# KMO_IO_MV2_1.net
KiCad netlist of a schematic drawn in EAGLE
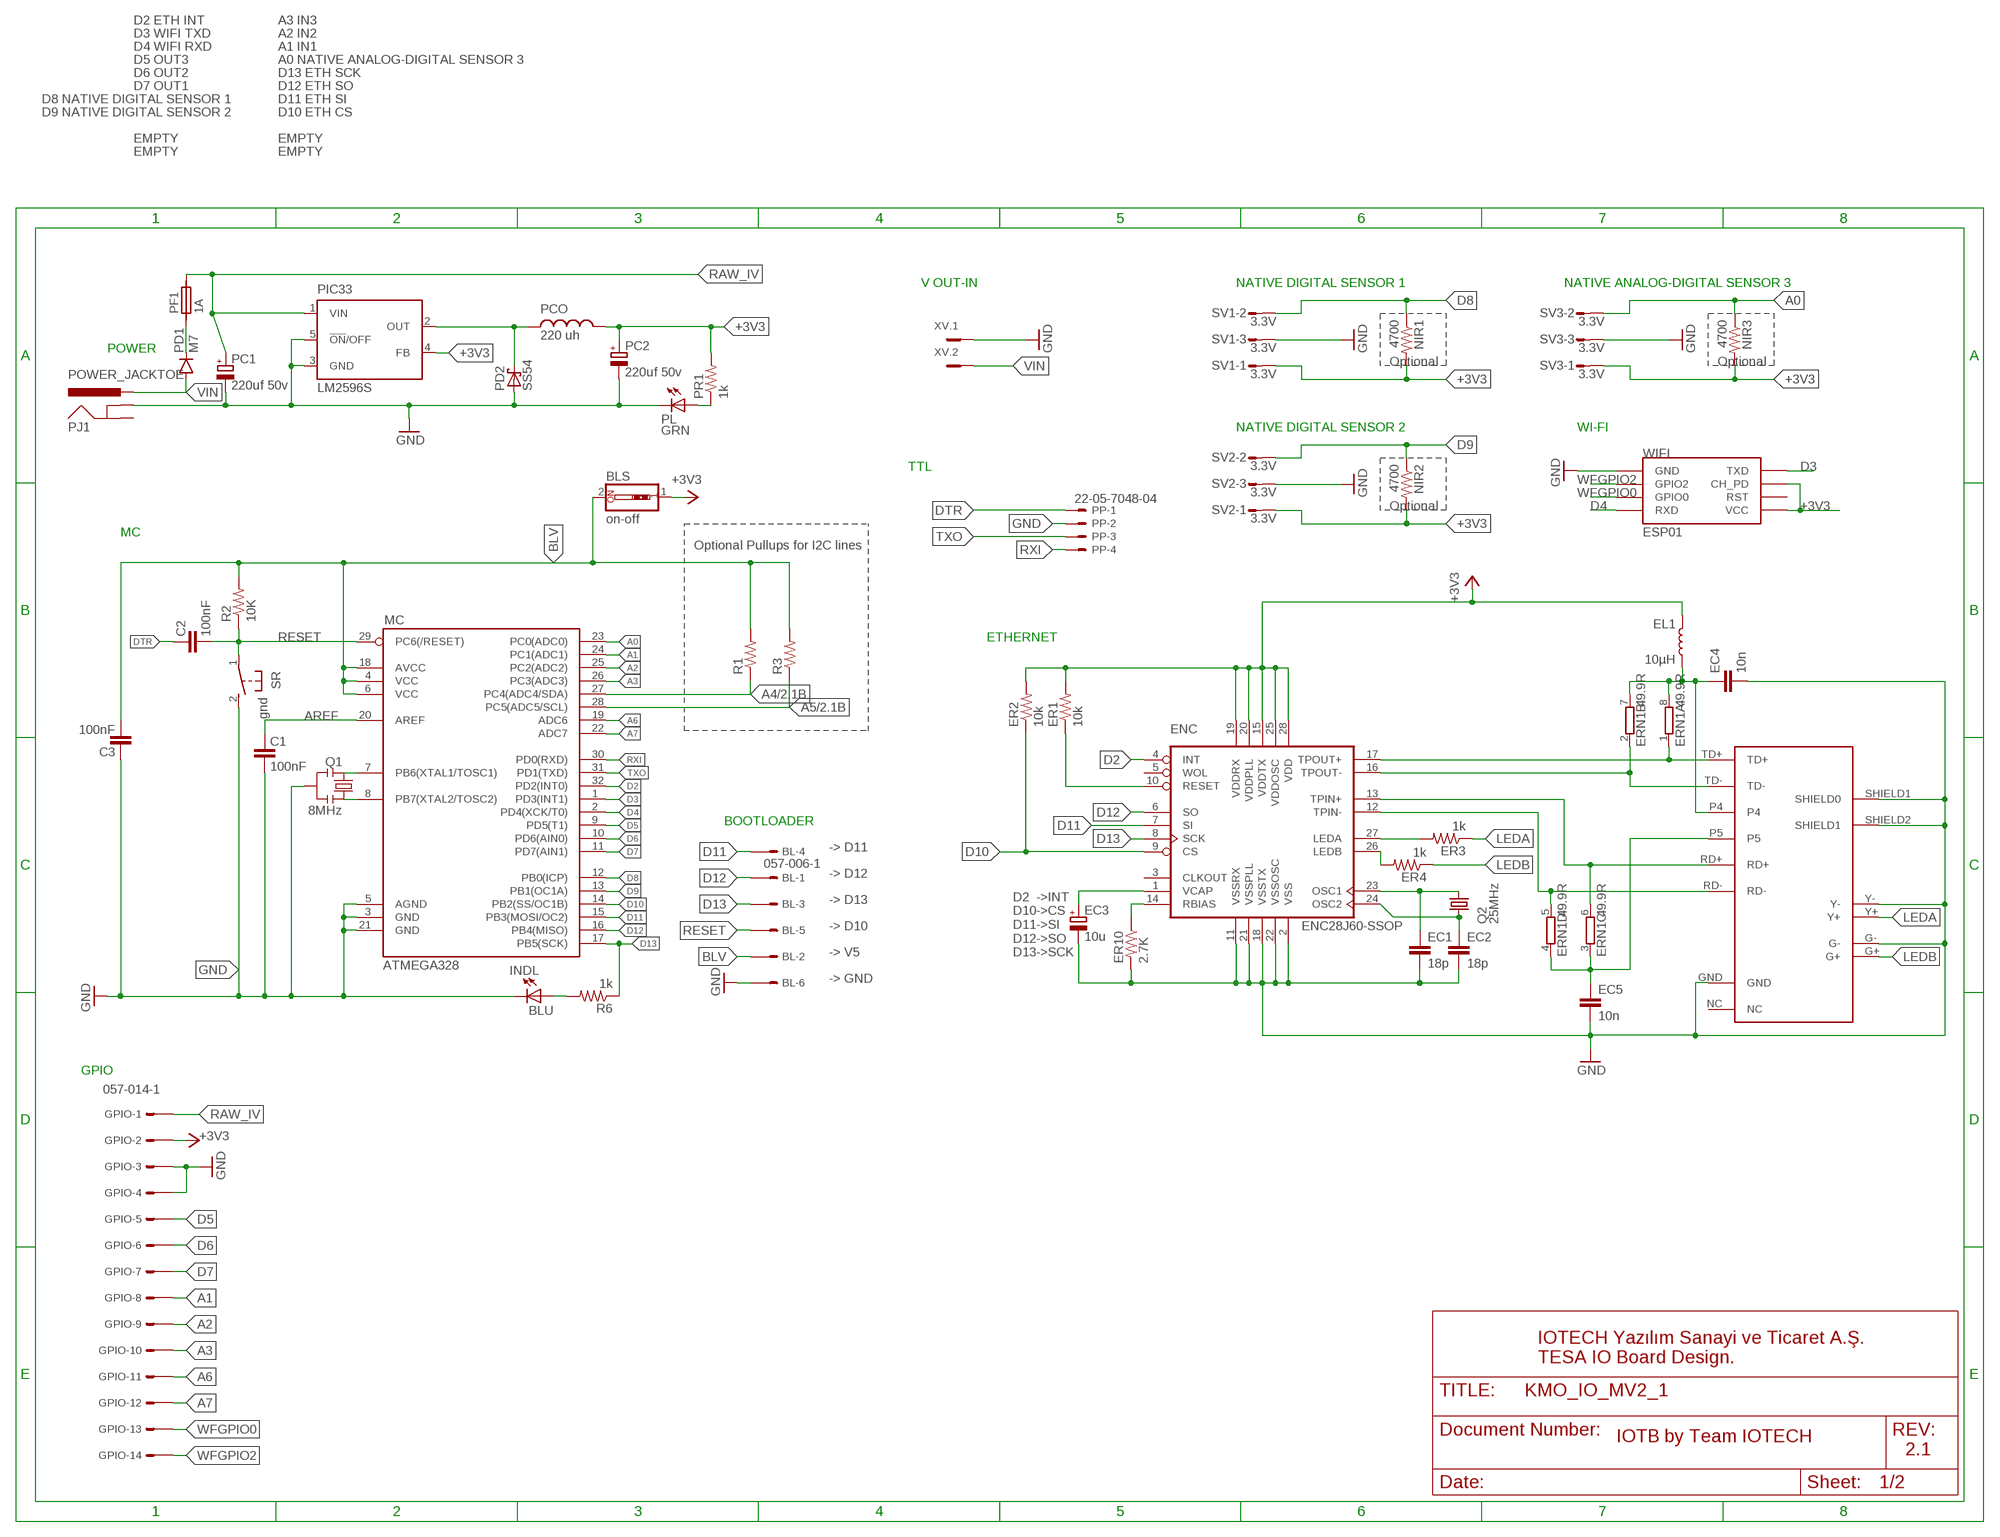
[diagram p0: schematic, sheet 1]
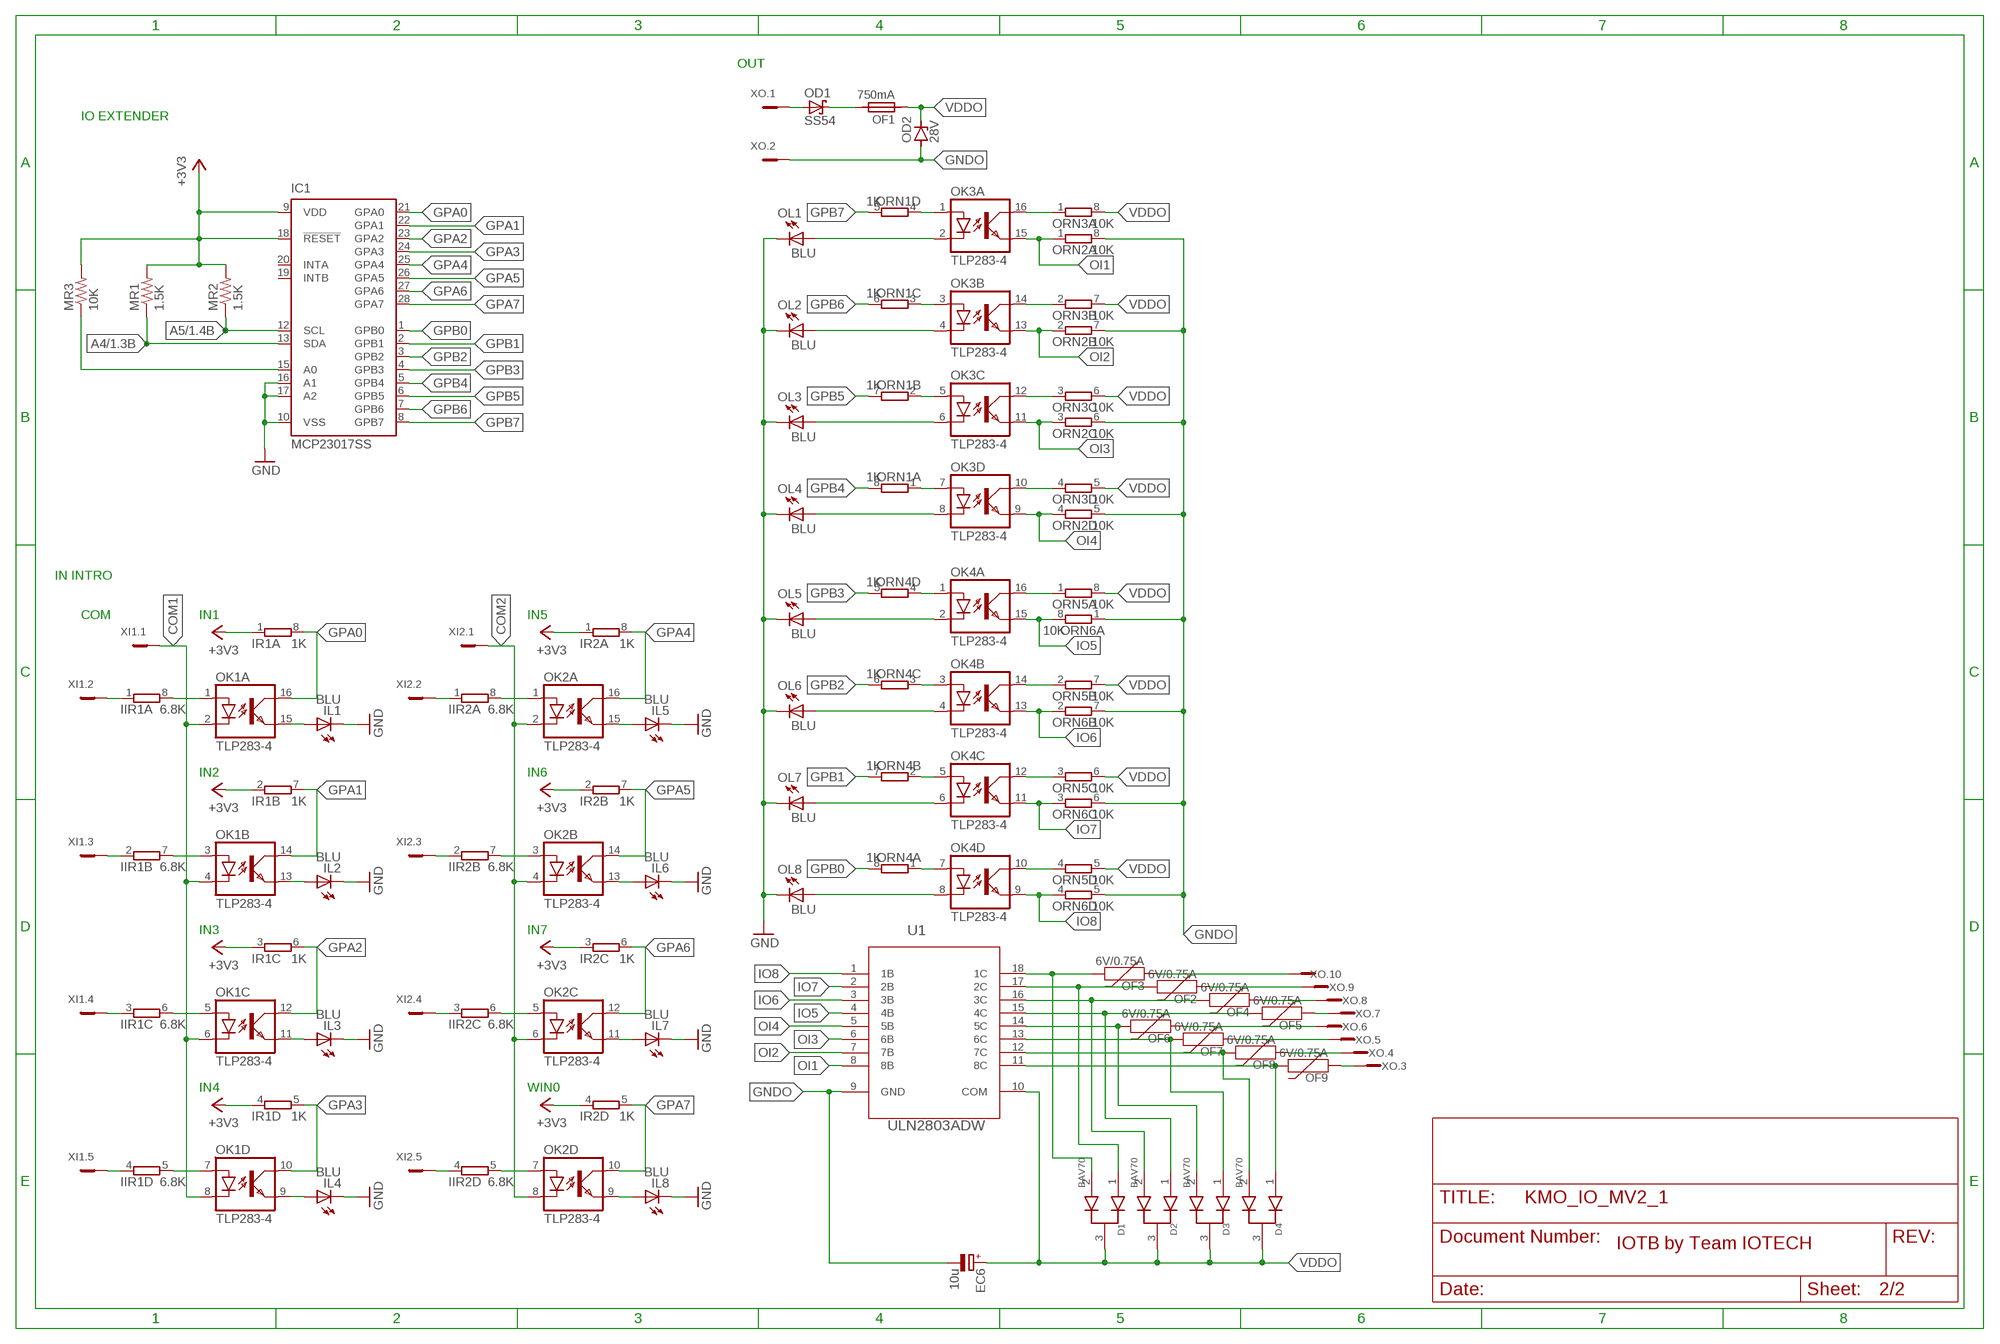
[diagram p1: schematic, sheet 2]

(export (version "E")
  (design (tool "Eeschema 10.0.6"))
  (components
    (comp (ref "BL")
      (value "057-006-1")
      (footprint "eagle-import:057-006-1")
      (libsource (lib "eagle-import") (part "057-006-1"))
    )
    (comp (ref "BLS")
      (value "on-off")
      (footprint "eagle-import:EDG-01")
      (libsource (lib "eagle-import") (part "SW_DIP-1"))
    )
    (comp (ref "C1")
      (value "100nF")
      (footprint "eagle-import:0805")
      (libsource (lib "eagle-import") (part "CAP0805"))
    )
    (comp (ref "C2")
      (value "100nF")
      (footprint "eagle-import:0805")
      (libsource (lib "eagle-import") (part "CAP0805"))
    )
    (comp (ref "C3")
      (value "100nF")
      (footprint "eagle-import:0805")
      (libsource (lib "eagle-import") (part "CAP0805"))
    )
    (comp (ref "EC1")
      (value "18p")
      (footprint "eagle-import:0805")
      (libsource (lib "eagle-import") (part "CAP0805"))
    )
    (comp (ref "EC2")
      (value "18p")
      (footprint "eagle-import:0805")
      (libsource (lib "eagle-import") (part "CAP0805"))
    )
    (comp (ref "EC3")
      (value "10u")
      (footprint "eagle-import:CT3216")
      (libsource (lib "eagle-import") (part "CPOL-EUCT3216"))
    )
    (comp (ref "EC4")
      (value "10n")
      (footprint "eagle-import:0805")
      (libsource (lib "eagle-import") (part "CAP0805"))
    )
    (comp (ref "EC5")
      (value "10n")
      (footprint "eagle-import:0805")
      (libsource (lib "eagle-import") (part "CAP0805"))
    )
    (comp (ref "EL1")
      (value "10µH")
      (footprint "eagle-import:0805")
      (libsource (lib "eagle-import") (part "INDUCTOR-0805-3.3UH"))
    )
    (comp (ref "ENC")
      (value "ENC28J60-SSOP")
      (footprint "eagle-import:SSOP28")
      (libsource (lib "eagle-import") (part "ENC28J60-SSOP"))
    )
    (comp (ref "ER1")
      (value "10k")
      (footprint "eagle-import:0805")
      (libsource (lib "eagle-import") (part "RESISTOR0805-RES"))
    )
    (comp (ref "ER2")
      (value "10k")
      (footprint "eagle-import:0805")
      (libsource (lib "eagle-import") (part "RESISTOR0805-RES"))
    )
    (comp (ref "ER3")
      (value "1k")
      (footprint "eagle-import:0805")
      (libsource (lib "eagle-import") (part "RESISTOR0805-RES"))
    )
    (comp (ref "ER4")
      (value "1k")
      (footprint "eagle-import:0805")
      (libsource (lib "eagle-import") (part "RESISTOR0805-RES"))
    )
    (comp (ref "ER10")
      (value "2.7K")
      (footprint "eagle-import:0805")
      (libsource (lib "eagle-import") (part "RESISTOR0805-RES"))
    )
    (comp (ref "ERN1")
      (value "49.9R")
      (footprint "eagle-import:0603-ARV")
      (libsource (lib "eagle-import") (part "4R-N0603-ARV"))
    )
    (comp (ref "GPIO")
      (value "057-014-1")
      (footprint "eagle-import:057-014-1")
      (libsource (lib "eagle-import") (part "057-014-1"))
    )
    (comp (ref "INDL")
      (value "BLU")
      (footprint "eagle-import:CHIP-LED0805")
      (libsource (lib "eagle-import") (part "LEDCHIP-LED0805"))
    )
    (comp (ref "MC")
      (value "ATMEGA328")
      (footprint "eagle-import:TQFP32-08")
      (libsource (lib "eagle-import") (part "ATMEGA168"))
    )
    (comp (ref "NIR1")
      (value "4700")
      (footprint "eagle-import:0805")
      (libsource (lib "eagle-import") (part "RESISTOR0805-RES"))
    )
    (comp (ref "NIR2")
      (value "4700")
      (footprint "eagle-import:0805")
      (libsource (lib "eagle-import") (part "RESISTOR0805-RES"))
    )
    (comp (ref "NIR3")
      (value "4700")
      (footprint "eagle-import:0805")
      (libsource (lib "eagle-import") (part "RESISTOR0805-RES"))
    )
    (comp (ref "PC1")
      (value "220uf 50v")
      (footprint "eagle-import:140CLH-1010")
      (libsource (lib "eagle-import") (part "CPOL-EU140CLH-1010"))
    )
    (comp (ref "PC2")
      (value "220uf 50v")
      (footprint "eagle-import:140CLH-1010")
      (libsource (lib "eagle-import") (part "CPOL-EU140CLH-1010"))
    )
    (comp (ref "PCO")
      (value "220 uh")
      (footprint "eagle-import:MSS1260")
      (libsource (lib "eagle-import") (part "MSS1260"))
    )
    (comp (ref "PD1")
      (value "M7")
      (footprint "eagle-import:SMA-DIODE")
      (libsource (lib "eagle-import") (part "DIODESMA"))
    )
    (comp (ref "PD2")
      (value "SS54")
      (footprint "eagle-import:SMB")
      (libsource (lib "eagle-import") (part "SCHOTTKY-DIODESMD"))
    )
    (comp (ref "PF1")
      (value "1A")
      (footprint "eagle-import:1820")
      (libsource (lib "eagle-import") (part "SIBA194600"))
    )
    (comp (ref "PIC33")
      (value "LM2596S")
      (footprint "eagle-import:TO263-5")
      (fields (field (name "MF") "NATIONAL SEMICONDUCTOR") (field (name "MPN") "LM2596S-ADJ/NOPB"))
      (libsource (lib "eagle-import") (part "LM2596S"))
    )
    (comp (ref "PJ1")
      (value "POWER_JACKTOE")
      (footprint "eagle-import:POWER_JACK_SMD_OVERPASTE_TOE")
      (libsource (lib "eagle-import") (part "POWER_JACKTOE"))
    )
    (comp (ref "PL")
      (value "GRN")
      (footprint "eagle-import:CHIP-LED0805")
      (libsource (lib "eagle-import") (part "LEDCHIP-LED0805"))
    )
    (comp (ref "PP")
      (value "22-05-7048-04")
      (footprint "eagle-import:7395-04")
      (fields (field (name "MF") "MOLEX"))
      (libsource (lib "eagle-import") (part "22-?-0405-7048"))
    )
    (comp (ref "PR1")
      (value "1k")
      (footprint "eagle-import:0805")
      (libsource (lib "eagle-import") (part "RESISTOR0805-RES"))
    )
    (comp (ref "Q1")
      (value "8MHz")
      (footprint "eagle-import:RESONATOR-SMD-1_1")
      (libsource (lib "eagle-import") (part "RESONATOR1{colon}1"))
    )
    (comp (ref "Q2")
      (value "25MHz")
      (footprint "eagle-import:5.0X3.2_2")
      (libsource (lib "eagle-import") (part "KX-9B"))
    )
    (comp (ref "R1")
      (value "RESISTOR0805-RES")
      (footprint "eagle-import:0805")
      (libsource (lib "eagle-import") (part "RESISTOR0805-RES"))
    )
    (comp (ref "R2")
      (value "10K")
      (footprint "eagle-import:0805")
      (libsource (lib "eagle-import") (part "RESISTOR0805-RES"))
    )
    (comp (ref "R3")
      (value "RESISTOR0805-RES")
      (footprint "eagle-import:0805")
      (libsource (lib "eagle-import") (part "RESISTOR0805-RES"))
    )
    (comp (ref "R6")
      (value "1k")
      (footprint "eagle-import:0805")
      (libsource (lib "eagle-import") (part "RESISTOR0805-RES"))
    )
    (comp (ref "SR")
      (value "gnd")
      (footprint "eagle-import:B3F-31XX")
      (fields (field (name "MPN") "B3F-3100"))
      (libsource (lib "eagle-import") (part "31-XX"))
    )
    (comp (ref "SV1")
      (value "3.3V")
      (footprint "eagle-import:S03P")
      (libsource (lib "eagle-import") (part "S03P"))
    )
    (comp (ref "SV2")
      (value "3.3V")
      (footprint "eagle-import:S03P")
      (libsource (lib "eagle-import") (part "S03P"))
    )
    (comp (ref "SV3")
      (value "3.3V")
      (footprint "eagle-import:S03P")
      (libsource (lib "eagle-import") (part "S03P"))
    )
    (comp (ref "U$2")
      (value "HR911105A")
      (footprint "eagle-import:RJ45")
      (libsource (lib "eagle-import") (part "HR911105A"))
    )
    (comp (ref "WIFI")
      (value "ESP01")
      (footprint "eagle-import:ESP01")
      (libsource (lib "eagle-import") (part "ESP01"))
    )
    (comp (ref "XV")
      (value "MC2")
      (footprint "eagle-import:MC2")
      (libsource (lib "eagle-import") (part "MC2"))
    )
    (comp (ref "D1")
      (value "BAV70")
      (footprint "eagle-import:SOT-23-3")
      (fields (field (name "MF") "Multicomp") (field (name "MP") "BAV70+"))
      (libsource (lib "eagle-import") (part "BAV70"))
    )
    (comp (ref "D2")
      (value "BAV70")
      (footprint "eagle-import:SOT-23-3")
      (fields (field (name "MF") "Multicomp") (field (name "MP") "BAV70+"))
      (libsource (lib "eagle-import") (part "BAV70"))
    )
    (comp (ref "D3")
      (value "BAV70")
      (footprint "eagle-import:SOT-23-3")
      (fields (field (name "MF") "Multicomp") (field (name "MP") "BAV70+"))
      (libsource (lib "eagle-import") (part "BAV70"))
    )
    (comp (ref "D4")
      (value "BAV70")
      (footprint "eagle-import:SOT-23-3")
      (fields (field (name "MF") "Multicomp") (field (name "MP") "BAV70+"))
      (libsource (lib "eagle-import") (part "BAV70"))
    )
    (comp (ref "EC6")
      (value "10u")
      (footprint "eagle-import:CT3216")
      (libsource (lib "eagle-import") (part "CPOL-EUCT3216"))
    )
    (comp (ref "IC1")
      (value "MCP23017SS")
      (footprint "eagle-import:SSOP28")
      (fields (field (name "MF") "MICROCHIP") (field (name "MPN") "MCP23017-E/SS"))
      (libsource (lib "eagle-import") (part "MCP23017SS"))
    )
    (comp (ref "IIR1")
      (value "6.8K")
      (footprint "eagle-import:0603-ARV")
      (libsource (lib "eagle-import") (part "4R-N0603-ARV"))
    )
    (comp (ref "IIR2")
      (value "6.8K")
      (footprint "eagle-import:0603-ARV")
      (libsource (lib "eagle-import") (part "4R-N0603-ARV"))
    )
    (comp (ref "IL1")
      (value "BLU")
      (footprint "eagle-import:CHIP-LED0805")
      (libsource (lib "eagle-import") (part "LEDCHIP-LED0805"))
    )
    (comp (ref "IL2")
      (value "BLU")
      (footprint "eagle-import:CHIP-LED0805")
      (libsource (lib "eagle-import") (part "LEDCHIP-LED0805"))
    )
    (comp (ref "IL3")
      (value "BLU")
      (footprint "eagle-import:CHIP-LED0805")
      (libsource (lib "eagle-import") (part "LEDCHIP-LED0805"))
    )
    (comp (ref "IL4")
      (value "BLU")
      (footprint "eagle-import:CHIP-LED0805")
      (libsource (lib "eagle-import") (part "LEDCHIP-LED0805"))
    )
    (comp (ref "IL5")
      (value "BLU")
      (footprint "eagle-import:CHIP-LED0805")
      (libsource (lib "eagle-import") (part "LEDCHIP-LED0805"))
    )
    (comp (ref "IL6")
      (value "BLU")
      (footprint "eagle-import:CHIP-LED0805")
      (libsource (lib "eagle-import") (part "LEDCHIP-LED0805"))
    )
    (comp (ref "IL7")
      (value "BLU")
      (footprint "eagle-import:CHIP-LED0805")
      (libsource (lib "eagle-import") (part "LEDCHIP-LED0805"))
    )
    (comp (ref "IL8")
      (value "BLU")
      (footprint "eagle-import:CHIP-LED0805")
      (libsource (lib "eagle-import") (part "LEDCHIP-LED0805"))
    )
    (comp (ref "IR1")
      (value "1K")
      (footprint "eagle-import:0603-ARV")
      (libsource (lib "eagle-import") (part "4R-N0603-ARV"))
    )
    (comp (ref "IR2")
      (value "1K")
      (footprint "eagle-import:0603-ARV")
      (libsource (lib "eagle-import") (part "4R-N0603-ARV"))
    )
    (comp (ref "MR1")
      (value "1.5K")
      (footprint "eagle-import:0805")
      (libsource (lib "eagle-import") (part "RESISTOR0805-RES"))
    )
    (comp (ref "MR2")
      (value "1.5K")
      (footprint "eagle-import:0805")
      (libsource (lib "eagle-import") (part "RESISTOR0805-RES"))
    )
    (comp (ref "MR3")
      (value "10K")
      (footprint "eagle-import:0805")
      (libsource (lib "eagle-import") (part "RESISTOR0805-RES"))
    )
    (comp (ref "OD1")
      (value "SS54")
      (footprint "eagle-import:SMB")
      (libsource (lib "eagle-import") (part "SCHOTTKY-DIODESMD"))
    )
    (comp (ref "OD2")
      (value "28V")
      (footprint "eagle-import:SMB")
      (libsource (lib "eagle-import") (part "ZENER-DIODESMB"))
    )
    (comp (ref "OF1")
      (value "750mA")
      (footprint "eagle-import:1820")
      (libsource (lib "eagle-import") (part "SIBA194600"))
    )
    (comp (ref "OF2")
      (value "6V/0.75A")
      (footprint "eagle-import:1206")
      (libsource (lib "eagle-import") (part "PPTC_0.75A"))
    )
    (comp (ref "OF3")
      (value "6V/0.75A")
      (footprint "eagle-import:1206")
      (libsource (lib "eagle-import") (part "PPTC_0.75A"))
    )
    (comp (ref "OF4")
      (value "6V/0.75A")
      (footprint "eagle-import:1206")
      (libsource (lib "eagle-import") (part "PPTC_0.75A"))
    )
    (comp (ref "OF5")
      (value "6V/0.75A")
      (footprint "eagle-import:1206")
      (libsource (lib "eagle-import") (part "PPTC_0.75A"))
    )
    (comp (ref "OF6")
      (value "6V/0.75A")
      (footprint "eagle-import:1206")
      (libsource (lib "eagle-import") (part "PPTC_0.75A"))
    )
    (comp (ref "OF7")
      (value "6V/0.75A")
      (footprint "eagle-import:1206")
      (libsource (lib "eagle-import") (part "PPTC_0.75A"))
    )
    (comp (ref "OF8")
      (value "6V/0.75A")
      (footprint "eagle-import:1206")
      (libsource (lib "eagle-import") (part "PPTC_0.75A"))
    )
    (comp (ref "OF9")
      (value "6V/0.75A")
      (footprint "eagle-import:1206")
      (libsource (lib "eagle-import") (part "PPTC_0.75A"))
    )
    (comp (ref "OK1")
      (value "TLP283-4")
      (footprint "eagle-import:MINI-FLAT-16")
      (fields (field (name "SPICEPREFIX") "O"))
      (libsource (lib "eagle-import") (part "TLP283-4"))
    )
    (comp (ref "OK2")
      (value "TLP283-4")
      (footprint "eagle-import:MINI-FLAT-16")
      (fields (field (name "SPICEPREFIX") "O"))
      (libsource (lib "eagle-import") (part "TLP283-4"))
    )
    (comp (ref "OK3")
      (value "TLP283-4")
      (footprint "eagle-import:MINI-FLAT-16")
      (libsource (lib "eagle-import") (part "TLP283-4"))
    )
    (comp (ref "OK4")
      (value "TLP283-4")
      (footprint "eagle-import:MINI-FLAT-16")
      (libsource (lib "eagle-import") (part "TLP283-4"))
    )
    (comp (ref "OL1")
      (value "BLU")
      (footprint "eagle-import:CHIP-LED0805")
      (libsource (lib "eagle-import") (part "LEDCHIP-LED0805"))
    )
    (comp (ref "OL2")
      (value "BLU")
      (footprint "eagle-import:CHIP-LED0805")
      (libsource (lib "eagle-import") (part "LEDCHIP-LED0805"))
    )
    (comp (ref "OL3")
      (value "BLU")
      (footprint "eagle-import:CHIP-LED0805")
      (libsource (lib "eagle-import") (part "LEDCHIP-LED0805"))
    )
    (comp (ref "OL4")
      (value "BLU")
      (footprint "eagle-import:CHIP-LED0805")
      (libsource (lib "eagle-import") (part "LEDCHIP-LED0805"))
    )
    (comp (ref "OL5")
      (value "BLU")
      (footprint "eagle-import:CHIP-LED0805")
      (libsource (lib "eagle-import") (part "LEDCHIP-LED0805"))
    )
    (comp (ref "OL6")
      (value "BLU")
      (footprint "eagle-import:CHIP-LED0805")
      (libsource (lib "eagle-import") (part "LEDCHIP-LED0805"))
    )
    (comp (ref "OL7")
      (value "BLU")
      (footprint "eagle-import:CHIP-LED0805")
      (libsource (lib "eagle-import") (part "LEDCHIP-LED0805"))
    )
    (comp (ref "OL8")
      (value "BLU")
      (footprint "eagle-import:CHIP-LED0805")
      (libsource (lib "eagle-import") (part "LEDCHIP-LED0805"))
    )
    (comp (ref "ORN1")
      (value "1K")
      (footprint "eagle-import:0603-ARV")
      (libsource (lib "eagle-import") (part "4R-N0603-ARV"))
    )
    (comp (ref "ORN2")
      (value "10K")
      (footprint "eagle-import:0603-ARV")
      (libsource (lib "eagle-import") (part "4R-N0603-ARV"))
    )
    (comp (ref "ORN3")
      (value "10K")
      (footprint "eagle-import:0603-ARV")
      (libsource (lib "eagle-import") (part "4R-N0603-ARV"))
    )
    (comp (ref "ORN4")
      (value "1K")
      (footprint "eagle-import:0603-ARV")
      (libsource (lib "eagle-import") (part "4R-N0603-ARV"))
    )
    (comp (ref "ORN5")
      (value "10K")
      (footprint "eagle-import:0603-ARV")
      (libsource (lib "eagle-import") (part "4R-N0603-ARV"))
    )
    (comp (ref "ORN6")
      (value "10K")
      (footprint "eagle-import:0603-ARV")
      (libsource (lib "eagle-import") (part "4R-N0603-ARV"))
    )
    (comp (ref "U1")
      (value "ULN2803ADW")
      (footprint "eagle-import:SOIC127P1030X265-18N")
      (libsource (lib "eagle-import") (part "ULN2803ADW"))
    )
    (comp (ref "XI1")
      (value "MC5")
      (footprint "eagle-import:MC5")
      (libsource (lib "eagle-import") (part "MC5"))
    )
    (comp (ref "XI2")
      (value "MC5")
      (footprint "eagle-import:MC5")
      (libsource (lib "eagle-import") (part "MC5"))
    )
    (comp (ref "XO")
      (value "MC10")
      (footprint "eagle-import:MC10")
      (libsource (lib "eagle-import") (part "MC10"))
    )
  )
  (nets
    (net (code "1") (name "+3V3") (class "Default")
      (node (ref "BLS") (pin "1") (pinfunction "1_1") (pintype "passive"))
      (node (ref "EL1") (pin "1") (pinfunction "1_1") (pintype "passive"))
      (node (ref "ENC") (pin "15") (pinfunction "VDDTX_15") (pintype "power_in"))
      (node (ref "ENC") (pin "19") (pinfunction "VDDRX_19") (pintype "power_in"))
      (node (ref "ENC") (pin "20") (pinfunction "VDDPLL_20") (pintype "power_in"))
      (node (ref "ENC") (pin "25") (pinfunction "VDDOSC_25") (pintype "power_in"))
      (node (ref "ENC") (pin "28") (pinfunction "VDD_28") (pintype "power_in"))
      (node (ref "ER1") (pin "2") (pinfunction "2_2") (pintype "passive"))
      (node (ref "ER2") (pin "2") (pinfunction "2_2") (pintype "passive"))
      (node (ref "GPIO") (pin "2") (pinfunction "S_2") (pintype "passive"))
      (node (ref "IC1") (pin "18") (pinfunction "~{RESET}_18") (pintype "input"))
      (node (ref "IC1") (pin "9") (pinfunction "VDD_9") (pintype "power_in"))
      (node (ref "IR1") (pin "1") (pinfunction "1_1") (pintype "passive"))
      (node (ref "IR1") (pin "2") (pinfunction "1_2") (pintype "passive"))
      (node (ref "IR1") (pin "3") (pinfunction "1_3") (pintype "passive"))
      (node (ref "IR1") (pin "4") (pinfunction "1_4") (pintype "passive"))
      (node (ref "IR2") (pin "1") (pinfunction "1_1") (pintype "passive"))
      (node (ref "IR2") (pin "2") (pinfunction "1_2") (pintype "passive"))
      (node (ref "IR2") (pin "3") (pinfunction "1_3") (pintype "passive"))
      (node (ref "IR2") (pin "4") (pinfunction "1_4") (pintype "passive"))
      (node (ref "MR1") (pin "2") (pinfunction "2_2") (pintype "passive"))
      (node (ref "MR2") (pin "2") (pinfunction "2_2") (pintype "passive"))
      (node (ref "MR3") (pin "2") (pinfunction "2_2") (pintype "passive"))
      (node (ref "NIR1") (pin "2") (pinfunction "2_2") (pintype "passive"))
      (node (ref "NIR2") (pin "2") (pinfunction "2_2") (pintype "passive"))
      (node (ref "NIR3") (pin "2") (pinfunction "2_2") (pintype "passive"))
      (node (ref "PC2") (pin "+") (pinfunction "+_+") (pintype "passive"))
      (node (ref "PCO") (pin "P$1") (pinfunction "P$1_P$1") (pintype "passive"))
      (node (ref "PIC33") (pin "4") (pinfunction "FB_4") (pintype "input"))
      (node (ref "PR1") (pin "2") (pinfunction "2_2") (pintype "passive"))
      (node (ref "SV1") (pin "1") (pinfunction "S_1") (pintype "passive"))
      (node (ref "SV2") (pin "1") (pinfunction "S_1") (pintype "passive"))
      (node (ref "SV3") (pin "1") (pinfunction "S_1") (pintype "passive"))
      (node (ref "WIFI") (pin "CH_PD") (pinfunction "CH_PD_CH_PD") (pintype "bidirectional"))
      (node (ref "WIFI") (pin "VCC") (pinfunction "VCC_VCC") (pintype "bidirectional"))
    )
    (net (code "2") (name "A0") (class "Default")
      (node (ref "MC") (pin "23") (pinfunction "PC0(ADC0)_23") (pintype "bidirectional"))
      (node (ref "NIR3") (pin "1") (pinfunction "1_1") (pintype "passive"))
      (node (ref "SV3") (pin "2") (pinfunction "S_2") (pintype "passive"))
    )
    (net (code "3") (name "A1") (class "Default")
      (node (ref "GPIO") (pin "8") (pinfunction "S_8") (pintype "passive"))
      (node (ref "MC") (pin "24") (pinfunction "PC1(ADC1)_24") (pintype "bidirectional"))
    )
    (net (code "4") (name "A2") (class "Default")
      (node (ref "GPIO") (pin "9") (pinfunction "S_9") (pintype "passive"))
      (node (ref "MC") (pin "25") (pinfunction "PC2(ADC2)_25") (pintype "bidirectional"))
    )
    (net (code "5") (name "A3") (class "Default")
      (node (ref "GPIO") (pin "10") (pinfunction "S_10") (pintype "passive"))
      (node (ref "MC") (pin "26") (pinfunction "PC3(ADC3)_26") (pintype "bidirectional"))
    )
    (net (code "6") (name "A4") (class "Default")
      (node (ref "IC1") (pin "13") (pinfunction "SDA_13") (pintype "bidirectional"))
      (node (ref "MC") (pin "27") (pinfunction "PC4(ADC4/SDA)_27") (pintype "bidirectional"))
      (node (ref "MR1") (pin "1") (pinfunction "1_1") (pintype "passive"))
      (node (ref "R1") (pin "1") (pinfunction "1_1") (pintype "passive"))
    )
    (net (code "7") (name "A5") (class "Default")
      (node (ref "IC1") (pin "12") (pinfunction "SCL_12") (pintype "input"))
      (node (ref "MC") (pin "28") (pinfunction "PC5(ADC5/SCL)_28") (pintype "bidirectional"))
      (node (ref "MR2") (pin "1") (pinfunction "1_1") (pintype "passive"))
      (node (ref "R3") (pin "1") (pinfunction "1_1") (pintype "passive"))
    )
    (net (code "8") (name "A6") (class "Default")
      (node (ref "GPIO") (pin "11") (pinfunction "S_11") (pintype "passive"))
      (node (ref "MC") (pin "19") (pinfunction "ADC6_19") (pintype "bidirectional"))
    )
    (net (code "9") (name "A7") (class "Default")
      (node (ref "GPIO") (pin "12") (pinfunction "S_12") (pintype "passive"))
      (node (ref "MC") (pin "22") (pinfunction "ADC7_22") (pintype "bidirectional"))
    )
    (net (code "10") (name "AREF") (class "Default")
      (node (ref "C1") (pin "2") (pinfunction "2_2") (pintype "passive"))
      (node (ref "MC") (pin "20") (pinfunction "AREF_20") (pintype "bidirectional"))
    )
    (net (code "11") (name "BLV") (class "Default")
      (node (ref "BL") (pin "2") (pinfunction "S_2") (pintype "passive"))
      (node (ref "BLS") (pin "2") (pinfunction "2_2") (pintype "passive"))
      (node (ref "C3") (pin "1") (pinfunction "1_1") (pintype "passive"))
      (node (ref "MC") (pin "18") (pinfunction "AVCC_18") (pintype "bidirectional"))
      (node (ref "MC") (pin "4") (pinfunction "VCC_4") (pintype "bidirectional"))
      (node (ref "MC") (pin "6") (pinfunction "VCC_6") (pintype "bidirectional"))
      (node (ref "R1") (pin "2") (pinfunction "2_2") (pintype "passive"))
      (node (ref "R2") (pin "2") (pinfunction "2_2") (pintype "passive"))
      (node (ref "R3") (pin "2") (pinfunction "2_2") (pintype "passive"))
    )
    (net (code "12") (name "COM1") (class "Default")
      (node (ref "OK1") (pin "2") (pinfunction "C_2") (pintype "passive"))
      (node (ref "OK1") (pin "4") (pinfunction "C_4") (pintype "passive"))
      (node (ref "OK1") (pin "6") (pinfunction "C_6") (pintype "passive"))
      (node (ref "OK1") (pin "8") (pinfunction "C_8") (pintype "passive"))
      (node (ref "XI1") (pin "1") (pinfunction "SK_1") (pintype "passive"))
    )
    (net (code "13") (name "COM2") (class "Default")
      (node (ref "OK2") (pin "2") (pinfunction "C_2") (pintype "passive"))
      (node (ref "OK2") (pin "4") (pinfunction "C_4") (pintype "passive"))
      (node (ref "OK2") (pin "6") (pinfunction "C_6") (pintype "passive"))
      (node (ref "OK2") (pin "8") (pinfunction "C_8") (pintype "passive"))
      (node (ref "XI2") (pin "1") (pinfunction "SK_1") (pintype "passive"))
    )
    (net (code "14") (name "D2") (class "Default")
      (node (ref "ENC") (pin "4") (pinfunction "INT_4") (pintype "output"))
      (node (ref "MC") (pin "32") (pinfunction "PD2(INT0)_32") (pintype "bidirectional"))
    )
    (net (code "15") (name "D3") (class "Default")
      (node (ref "MC") (pin "1") (pinfunction "PD3(INT1)_1") (pintype "bidirectional"))
      (node (ref "WIFI") (pin "TX") (pinfunction "TXD_TX") (pintype "bidirectional"))
    )
    (net (code "16") (name "D4") (class "Default")
      (node (ref "MC") (pin "2") (pinfunction "PD4(XCK/T0)_2") (pintype "bidirectional"))
      (node (ref "WIFI") (pin "RX") (pinfunction "RXD_RX") (pintype "bidirectional"))
    )
    (net (code "17") (name "D5") (class "Default")
      (node (ref "GPIO") (pin "5") (pinfunction "S_5") (pintype "passive"))
      (node (ref "MC") (pin "9") (pinfunction "PD5(T1)_9") (pintype "bidirectional"))
    )
    (net (code "18") (name "D6") (class "Default")
      (node (ref "GPIO") (pin "6") (pinfunction "S_6") (pintype "passive"))
      (node (ref "MC") (pin "10") (pinfunction "PD6(AIN0)_10") (pintype "bidirectional"))
    )
    (net (code "19") (name "D7") (class "Default")
      (node (ref "GPIO") (pin "7") (pinfunction "S_7") (pintype "passive"))
      (node (ref "MC") (pin "11") (pinfunction "PD7(AIN1)_11") (pintype "bidirectional"))
    )
    (net (code "20") (name "D8") (class "Default")
      (node (ref "MC") (pin "12") (pinfunction "PB0(ICP)_12") (pintype "bidirectional"))
      (node (ref "NIR1") (pin "1") (pinfunction "1_1") (pintype "passive"))
      (node (ref "SV1") (pin "2") (pinfunction "S_2") (pintype "passive"))
    )
    (net (code "21") (name "D9") (class "Default")
      (node (ref "MC") (pin "13") (pinfunction "PB1(OC1A)_13") (pintype "bidirectional"))
      (node (ref "NIR2") (pin "1") (pinfunction "1_1") (pintype "passive"))
      (node (ref "SV2") (pin "2") (pinfunction "S_2") (pintype "passive"))
    )
    (net (code "22") (name "D10") (class "Default")
      (node (ref "ENC") (pin "9") (pinfunction "CS_9") (pintype "input"))
      (node (ref "ER2") (pin "1") (pinfunction "1_1") (pintype "passive"))
      (node (ref "MC") (pin "14") (pinfunction "PB2(SS/OC1B)_14") (pintype "bidirectional"))
    )
    (net (code "23") (name "D11") (class "Default")
      (node (ref "BL") (pin "4") (pinfunction "S_4") (pintype "passive"))
      (node (ref "ENC") (pin "7") (pinfunction "SI_7") (pintype "input"))
      (node (ref "MC") (pin "15") (pinfunction "PB3(MOSI/OC2)_15") (pintype "bidirectional"))
    )
    (net (code "24") (name "D12") (class "Default")
      (node (ref "BL") (pin "1") (pinfunction "S_1") (pintype "passive"))
      (node (ref "ENC") (pin "6") (pinfunction "SO_6") (pintype "output"))
      (node (ref "MC") (pin "16") (pinfunction "PB4(MISO)_16") (pintype "bidirectional"))
    )
    (net (code "25") (name "D13") (class "Default")
      (node (ref "BL") (pin "3") (pinfunction "S_3") (pintype "passive"))
      (node (ref "ENC") (pin "8") (pinfunction "SCK_8") (pintype "input"))
      (node (ref "MC") (pin "17") (pinfunction "PB5(SCK)_17") (pintype "bidirectional"))
      (node (ref "R6") (pin "1") (pinfunction "1_1") (pintype "passive"))
    )
    (net (code "26") (name "DTR") (class "Default")
      (node (ref "C2") (pin "2") (pinfunction "2_2") (pintype "passive"))
      (node (ref "PP") (pin "1") (pinfunction "S_1") (pintype "passive"))
    )
    (net (code "27") (name "GND") (class "Default")
      (node (ref "BL") (pin "6") (pinfunction "S_6") (pintype "passive"))
      (node (ref "C1") (pin "1") (pinfunction "1_1") (pintype "passive"))
      (node (ref "C3") (pin "2") (pinfunction "2_2") (pintype "passive"))
      (node (ref "EC1") (pin "2") (pinfunction "2_2") (pintype "passive"))
      (node (ref "EC2") (pin "2") (pinfunction "2_2") (pintype "passive"))
      (node (ref "EC3") (pin "-") (pinfunction "-_-") (pintype "passive"))
      (node (ref "EC4") (pin "2") (pinfunction "2_2") (pintype "passive"))
      (node (ref "EC5") (pin "2") (pinfunction "2_2") (pintype "passive"))
      (node (ref "ENC") (pin "11") (pinfunction "VSSRX_11") (pintype "power_in"))
      (node (ref "ENC") (pin "18") (pinfunction "VSSTX_18") (pintype "power_in"))
      (node (ref "ENC") (pin "2") (pinfunction "VSS_2") (pintype "power_in"))
      (node (ref "ENC") (pin "21") (pinfunction "VSSPLL_21") (pintype "power_in"))
      (node (ref "ENC") (pin "22") (pinfunction "VSSOSC_22") (pintype "power_in"))
      (node (ref "ER10") (pin "2") (pinfunction "2_2") (pintype "passive"))
      (node (ref "GPIO") (pin "3") (pinfunction "S_3") (pintype "passive"))
      (node (ref "GPIO") (pin "4") (pinfunction "S_4") (pintype "passive"))
      (node (ref "IC1") (pin "10") (pinfunction "VSS_10") (pintype "power_in"))
      (node (ref "IC1") (pin "16") (pinfunction "A1_16") (pintype "input"))
      (node (ref "IC1") (pin "17") (pinfunction "A2_17") (pintype "input"))
      (node (ref "IL1") (pin "C") (pinfunction "C_C") (pintype "passive"))
      (node (ref "IL2") (pin "C") (pinfunction "C_C") (pintype "passive"))
      (node (ref "IL3") (pin "C") (pinfunction "C_C") (pintype "passive"))
      (node (ref "IL4") (pin "C") (pinfunction "C_C") (pintype "passive"))
      (node (ref "IL5") (pin "C") (pinfunction "C_C") (pintype "passive"))
      (node (ref "IL6") (pin "C") (pinfunction "C_C") (pintype "passive"))
      (node (ref "IL7") (pin "C") (pinfunction "C_C") (pintype "passive"))
      (node (ref "IL8") (pin "C") (pinfunction "C_C") (pintype "passive"))
      (node (ref "INDL") (pin "C") (pinfunction "C_C") (pintype "passive"))
      (node (ref "MC") (pin "21") (pinfunction "GND_21") (pintype "bidirectional"))
      (node (ref "MC") (pin "3") (pinfunction "GND_3") (pintype "bidirectional"))
      (node (ref "MC") (pin "5") (pinfunction "AGND_5") (pintype "bidirectional"))
      (node (ref "OL1") (pin "C") (pinfunction "C_C") (pintype "passive"))
      (node (ref "OL2") (pin "C") (pinfunction "C_C") (pintype "passive"))
      (node (ref "OL3") (pin "C") (pinfunction "C_C") (pintype "passive"))
      (node (ref "OL4") (pin "C") (pinfunction "C_C") (pintype "passive"))
      (node (ref "OL5") (pin "C") (pinfunction "C_C") (pintype "passive"))
      (node (ref "OL6") (pin "C") (pinfunction "C_C") (pintype "passive"))
      (node (ref "OL7") (pin "C") (pinfunction "C_C") (pintype "passive"))
      (node (ref "OL8") (pin "C") (pinfunction "C_C") (pintype "passive"))
      (node (ref "PC1") (pin "-") (pinfunction "-_-") (pintype "passive"))
      (node (ref "PC2") (pin "-") (pinfunction "-_-") (pintype "passive"))
      (node (ref "PD2") (pin "A") (pinfunction "A_A") (pintype "passive"))
      (node (ref "PIC33") (pin "3") (pinfunction "GND_3") (pintype "power_in"))
      (node (ref "PIC33") (pin "5") (pinfunction "~{ON}/OFF_5") (pintype "input"))
      (node (ref "PJ1") (pin "GND") (pinfunction "GNDBREAK_GND") (pintype "bidirectional"))
      (node (ref "PL") (pin "C") (pinfunction "C_C") (pintype "passive"))
      (node (ref "PP") (pin "2") (pinfunction "S_2") (pintype "passive"))
      (node (ref "Q1") (pin "2") (pinfunction "2_2") (pintype "passive"))
      (node (ref "SR") (pin "2") (pinfunction "S_2") (pintype "passive"))
      (node (ref "SV1") (pin "3") (pinfunction "S_3") (pintype "passive"))
      (node (ref "SV2") (pin "3") (pinfunction "S_3") (pintype "passive"))
      (node (ref "SV3") (pin "3") (pinfunction "S_3") (pintype "passive"))
      (node (ref "U$2") (pin "G-") (pinfunction "G-_G-") (pintype "bidirectional"))
      (node (ref "U$2") (pin "GND") (pinfunction "GND_GND") (pintype "bidirectional"))
      (node (ref "U$2") (pin "SHIELD1") (pinfunction "SHIELD0_SHIELD1") (pintype "bidirectional"))
      (node (ref "U$2") (pin "SHIELD2") (pinfunction "SHIELD1_SHIELD2") (pintype "bidirectional"))
      (node (ref "U$2") (pin "Y-") (pinfunction "Y-_Y-") (pintype "bidirectional"))
      (node (ref "WIFI") (pin "GND") (pinfunction "GND_GND") (pintype "bidirectional"))
      (node (ref "XV") (pin "1") (pinfunction "SK_1") (pintype "passive"))
    )
    (net (code "28") (name "GNDO") (class "Default")
      (node (ref "EC6") (pin "-") (pinfunction "-_-") (pintype "passive"))
      (node (ref "OD2") (pin "A") (pinfunction "A_A") (pintype "passive"))
      (node (ref "ORN2") (pin "5") (pinfunction "2_5") (pintype "passive"))
      (node (ref "ORN2") (pin "6") (pinfunction "2_6") (pintype "passive"))
      (node (ref "ORN2") (pin "7") (pinfunction "2_7") (pintype "passive"))
      (node (ref "ORN2") (pin "8") (pinfunction "2_8") (pintype "passive"))
      (node (ref "ORN6") (pin "1") (pinfunction "1_1") (pintype "passive"))
      (node (ref "ORN6") (pin "5") (pinfunction "2_5") (pintype "passive"))
      (node (ref "ORN6") (pin "6") (pinfunction "2_6") (pintype "passive"))
      (node (ref "ORN6") (pin "7") (pinfunction "2_7") (pintype "passive"))
      (node (ref "U1") (pin "9") (pinfunction "GND_9") (pintype "passive"))
      (node (ref "XO") (pin "2") (pinfunction "SK_2") (pintype "passive"))
    )
    (net (code "29") (name "GPA0") (class "Default")
      (node (ref "IC1") (pin "21") (pinfunction "GPA0_21") (pintype "bidirectional"))
      (node (ref "IR1") (pin "8") (pinfunction "2_8") (pintype "passive"))
      (node (ref "OK1") (pin "16") (pinfunction "COL_16") (pintype "passive"))
    )
    (net (code "30") (name "GPA1") (class "Default")
      (node (ref "IC1") (pin "22") (pinfunction "GPA1_22") (pintype "bidirectional"))
      (node (ref "IR1") (pin "7") (pinfunction "2_7") (pintype "passive"))
      (node (ref "OK1") (pin "14") (pinfunction "COL_14") (pintype "passive"))
    )
    (net (code "31") (name "GPA2") (class "Default")
      (node (ref "IC1") (pin "23") (pinfunction "GPA2_23") (pintype "bidirectional"))
      (node (ref "IR1") (pin "6") (pinfunction "2_6") (pintype "passive"))
      (node (ref "OK1") (pin "12") (pinfunction "COL_12") (pintype "passive"))
    )
    (net (code "32") (name "GPA3") (class "Default")
      (node (ref "IC1") (pin "24") (pinfunction "GPA3_24") (pintype "bidirectional"))
      (node (ref "IR1") (pin "5") (pinfunction "2_5") (pintype "passive"))
      (node (ref "OK1") (pin "10") (pinfunction "COL_10") (pintype "passive"))
    )
    (net (code "33") (name "GPA4") (class "Default")
      (node (ref "IC1") (pin "25") (pinfunction "GPA4_25") (pintype "bidirectional"))
      (node (ref "IR2") (pin "8") (pinfunction "2_8") (pintype "passive"))
      (node (ref "OK2") (pin "16") (pinfunction "COL_16") (pintype "passive"))
    )
    (net (code "34") (name "GPA5") (class "Default")
      (node (ref "IC1") (pin "26") (pinfunction "GPA5_26") (pintype "bidirectional"))
      (node (ref "IR2") (pin "7") (pinfunction "2_7") (pintype "passive"))
      (node (ref "OK2") (pin "14") (pinfunction "COL_14") (pintype "passive"))
    )
    (net (code "35") (name "GPA6") (class "Default")
      (node (ref "IC1") (pin "27") (pinfunction "GPA6_27") (pintype "bidirectional"))
      (node (ref "IR2") (pin "6") (pinfunction "2_6") (pintype "passive"))
      (node (ref "OK2") (pin "12") (pinfunction "COL_12") (pintype "passive"))
    )
    (net (code "36") (name "GPA7") (class "Default")
      (node (ref "IC1") (pin "28") (pinfunction "GPA7_28") (pintype "bidirectional"))
      (node (ref "IR2") (pin "5") (pinfunction "2_5") (pintype "passive"))
      (node (ref "OK2") (pin "10") (pinfunction "COL_10") (pintype "passive"))
    )
    (net (code "37") (name "GPB0") (class "Default")
      (node (ref "IC1") (pin "1") (pinfunction "GPB0_1") (pintype "bidirectional"))
      (node (ref "ORN4") (pin "8") (pinfunction "2_8") (pintype "passive"))
    )
    (net (code "38") (name "GPB1") (class "Default")
      (node (ref "IC1") (pin "2") (pinfunction "GPB1_2") (pintype "bidirectional"))
      (node (ref "ORN4") (pin "7") (pinfunction "2_7") (pintype "passive"))
    )
    (net (code "39") (name "GPB2") (class "Default")
      (node (ref "IC1") (pin "3") (pinfunction "GPB2_3") (pintype "bidirectional"))
      (node (ref "ORN4") (pin "6") (pinfunction "2_6") (pintype "passive"))
    )
    (net (code "40") (name "GPB3") (class "Default")
      (node (ref "IC1") (pin "4") (pinfunction "GPB3_4") (pintype "bidirectional"))
      (node (ref "ORN4") (pin "5") (pinfunction "2_5") (pintype "passive"))
    )
    (net (code "41") (name "GPB4") (class "Default")
      (node (ref "IC1") (pin "5") (pinfunction "GPB4_5") (pintype "bidirectional"))
      (node (ref "ORN1") (pin "8") (pinfunction "2_8") (pintype "passive"))
    )
    (net (code "42") (name "GPB5") (class "Default")
      (node (ref "IC1") (pin "6") (pinfunction "GPB5_6") (pintype "bidirectional"))
      (node (ref "ORN1") (pin "7") (pinfunction "2_7") (pintype "passive"))
    )
    (net (code "43") (name "GPB6") (class "Default")
      (node (ref "IC1") (pin "7") (pinfunction "GPB6_7") (pintype "bidirectional"))
      (node (ref "ORN1") (pin "6") (pinfunction "2_6") (pintype "passive"))
    )
    (net (code "44") (name "GPB7") (class "Default")
      (node (ref "IC1") (pin "8") (pinfunction "GPB7_8") (pintype "bidirectional"))
      (node (ref "ORN1") (pin "5") (pinfunction "2_5") (pintype "passive"))
    )
    (net (code "45") (name "IO5") (class "Default")
      (node (ref "OK4") (pin "15") (pinfunction "EMIT_15") (pintype "passive"))
      (node (ref "ORN6") (pin "8") (pinfunction "2_8") (pintype "passive"))
      (node (ref "U1") (pin "4") (pinfunction "4B_4") (pintype "input"))
    )
    (net (code "46") (name "IO6") (class "Default")
      (node (ref "OK4") (pin "13") (pinfunction "EMIT_13") (pintype "passive"))
      (node (ref "ORN6") (pin "2") (pinfunction "1_2") (pintype "passive"))
      (node (ref "U1") (pin "3") (pinfunction "3B_3") (pintype "input"))
    )
    (net (code "47") (name "IO7") (class "Default")
      (node (ref "OK4") (pin "11") (pinfunction "EMIT_11") (pintype "passive"))
      (node (ref "ORN6") (pin "3") (pinfunction "1_3") (pintype "passive"))
      (node (ref "U1") (pin "2") (pinfunction "2B_2") (pintype "input"))
    )
    (net (code "48") (name "IO8") (class "Default")
      (node (ref "OK4") (pin "9") (pinfunction "EMIT_9") (pintype "passive"))
      (node (ref "ORN6") (pin "4") (pinfunction "1_4") (pintype "passive"))
      (node (ref "U1") (pin "1") (pinfunction "1B_1") (pintype "input"))
    )
    (net (code "49") (name "LEDA") (class "Default")
      (node (ref "ER3") (pin "1") (pinfunction "1_1") (pintype "passive"))
      (node (ref "U$2") (pin "Y+") (pinfunction "Y+_Y+") (pintype "bidirectional"))
    )
    (net (code "50") (name "LEDB") (class "Default")
      (node (ref "ER4") (pin "1") (pinfunction "1_1") (pintype "passive"))
      (node (ref "U$2") (pin "G+") (pinfunction "G+_G+") (pintype "bidirectional"))
    )
    (net (code "51") (name "Net-(ENC-LEDA)") (class "Default")
      (node (ref "ENC") (pin "27") (pinfunction "LEDA_27") (pintype "output"))
      (node (ref "ER3") (pin "2") (pinfunction "2_2") (pintype "passive"))
    )
    (net (code "52") (name "Net-(ENC-LEDB)") (class "Default")
      (node (ref "ENC") (pin "26") (pinfunction "LEDB_26") (pintype "output"))
      (node (ref "ER4") (pin "2") (pinfunction "2_2") (pintype "passive"))
    )
    (net (code "53") (name "Net-(ENC-OSC1)") (class "Default")
      (node (ref "EC1") (pin "1") (pinfunction "1_1") (pintype "passive"))
      (node (ref "ENC") (pin "23") (pinfunction "OSC1_23") (pintype "input"))
      (node (ref "Q2") (pin "2") (pinfunction "2_2") (pintype "passive"))
    )
    (net (code "54") (name "Net-(ENC-OSC2)") (class "Default")
      (node (ref "EC2") (pin "1") (pinfunction "1_1") (pintype "passive"))
      (node (ref "ENC") (pin "24") (pinfunction "OSC2_24") (pintype "output"))
      (node (ref "Q2") (pin "1") (pinfunction "1_1") (pintype "passive"))
    )
    (net (code "55") (name "Net-(ENC-RBIAS)") (class "Default")
      (node (ref "ENC") (pin "14") (pinfunction "RBIAS_14") (pintype "passive"))
      (node (ref "ER10") (pin "1") (pinfunction "1_1") (pintype "passive"))
    )
    (net (code "56") (name "Net-(ENC-RESET)") (class "Default")
      (node (ref "ENC") (pin "10") (pinfunction "RESET_10") (pintype "input"))
      (node (ref "ER1") (pin "1") (pinfunction "1_1") (pintype "passive"))
    )
    (net (code "57") (name "Net-(ENC-TPIN+)") (class "Default")
      (node (ref "ENC") (pin "13") (pinfunction "TPIN+_13") (pintype "input"))
      (node (ref "ERN1") (pin "6") (pinfunction "2_6") (pintype "passive"))
      (node (ref "U$2") (pin "RD+") (pinfunction "RD+_RD+") (pintype "bidirectional"))
    )
    (net (code "58") (name "Net-(ENC-TPIN-)") (class "Default")
      (node (ref "ENC") (pin "12") (pinfunction "TPIN-_12") (pintype "input"))
      (node (ref "ERN1") (pin "5") (pinfunction "2_5") (pintype "passive"))
      (node (ref "U$2") (pin "RD-") (pinfunction "RD-_RD-") (pintype "bidirectional"))
    )
    (net (code "59") (name "Net-(ENC-TPOUT+)") (class "Default")
      (node (ref "ENC") (pin "17") (pinfunction "TPOUT+_17") (pintype "output"))
      (node (ref "ERN1") (pin "1") (pinfunction "1_1") (pintype "passive"))
      (node (ref "U$2") (pin "TD+") (pinfunction "TD+_TD+") (pintype "bidirectional"))
    )
    (net (code "60") (name "Net-(ENC-TPOUT-)") (class "Default")
      (node (ref "ENC") (pin "16") (pinfunction "TPOUT-_16") (pintype "output"))
      (node (ref "ERN1") (pin "2") (pinfunction "1_2") (pintype "passive"))
      (node (ref "U$2") (pin "TD-") (pinfunction "TD-_TD-") (pintype "bidirectional"))
    )
    (net (code "61") (name "Net-(ENC-VCAP)") (class "Default")
      (node (ref "EC3") (pin "+") (pinfunction "+_+") (pintype "passive"))
      (node (ref "ENC") (pin "1") (pinfunction "VCAP_1") (pintype "power_in"))
    )
    (net (code "62") (name "Net-(ERN1A-2)") (class "Default")
      (node (ref "EC4") (pin "1") (pinfunction "1_1") (pintype "passive"))
      (node (ref "EL1") (pin "2") (pinfunction "2_2") (pintype "passive"))
      (node (ref "ERN1") (pin "7") (pinfunction "2_7") (pintype "passive"))
      (node (ref "ERN1") (pin "8") (pinfunction "2_8") (pintype "passive"))
      (node (ref "U$2") (pin "P4") (pinfunction "P4_P4") (pintype "bidirectional"))
    )
    (net (code "63") (name "Net-(ERN1C-1)") (class "Default")
      (node (ref "EC5") (pin "1") (pinfunction "1_1") (pintype "passive"))
      (node (ref "ERN1") (pin "3") (pinfunction "1_3") (pintype "passive"))
      (node (ref "ERN1") (pin "4") (pinfunction "1_4") (pintype "passive"))
      (node (ref "U$2") (pin "P5") (pinfunction "P5_P5") (pintype "bidirectional"))
    )
    (net (code "64") (name "Net-(IC1-A0)") (class "Default")
      (node (ref "IC1") (pin "15") (pinfunction "A0_15") (pintype "input"))
      (node (ref "MR3") (pin "1") (pinfunction "1_1") (pintype "passive"))
    )
    (net (code "65") (name "Net-(IIR1A-2)") (class "Default")
      (node (ref "IIR1") (pin "8") (pinfunction "2_8") (pintype "passive"))
      (node (ref "OK1") (pin "1") (pinfunction "A_1") (pintype "passive"))
    )
    (net (code "66") (name "Net-(IIR1B-1)") (class "Default")
      (node (ref "IIR1") (pin "2") (pinfunction "1_2") (pintype "passive"))
      (node (ref "XI1") (pin "3") (pinfunction "SK_3") (pintype "passive"))
    )
    (net (code "67") (name "Net-(IIR1B-2)") (class "Default")
      (node (ref "IIR1") (pin "7") (pinfunction "2_7") (pintype "passive"))
      (node (ref "OK1") (pin "3") (pinfunction "A_3") (pintype "passive"))
    )
    (net (code "68") (name "Net-(IIR1C-1)") (class "Default")
      (node (ref "IIR1") (pin "3") (pinfunction "1_3") (pintype "passive"))
      (node (ref "XI1") (pin "4") (pinfunction "SK_4") (pintype "passive"))
    )
    (net (code "69") (name "Net-(IIR1C-2)") (class "Default")
      (node (ref "IIR1") (pin "6") (pinfunction "2_6") (pintype "passive"))
      (node (ref "OK1") (pin "5") (pinfunction "A_5") (pintype "passive"))
    )
    (net (code "70") (name "Net-(IIR1D-1)") (class "Default")
      (node (ref "IIR1") (pin "4") (pinfunction "1_4") (pintype "passive"))
      (node (ref "XI1") (pin "5") (pinfunction "SK_5") (pintype "passive"))
    )
    (net (code "71") (name "Net-(IIR1D-2)") (class "Default")
      (node (ref "IIR1") (pin "5") (pinfunction "2_5") (pintype "passive"))
      (node (ref "OK1") (pin "7") (pinfunction "A_7") (pintype "passive"))
    )
    (net (code "72") (name "Net-(IIR2A-2)") (class "Default")
      (node (ref "IIR2") (pin "8") (pinfunction "2_8") (pintype "passive"))
      (node (ref "OK2") (pin "1") (pinfunction "A_1") (pintype "passive"))
    )
    (net (code "73") (name "Net-(IIR2B-1)") (class "Default")
      (node (ref "IIR2") (pin "2") (pinfunction "1_2") (pintype "passive"))
      (node (ref "XI2") (pin "3") (pinfunction "SK_3") (pintype "passive"))
    )
    (net (code "74") (name "Net-(IIR2B-2)") (class "Default")
      (node (ref "IIR2") (pin "7") (pinfunction "2_7") (pintype "passive"))
      (node (ref "OK2") (pin "3") (pinfunction "A_3") (pintype "passive"))
    )
    (net (code "75") (name "Net-(IIR2C-1)") (class "Default")
      (node (ref "IIR2") (pin "3") (pinfunction "1_3") (pintype "passive"))
      (node (ref "XI2") (pin "4") (pinfunction "SK_4") (pintype "passive"))
    )
    (net (code "76") (name "Net-(IIR2C-2)") (class "Default")
      (node (ref "IIR2") (pin "6") (pinfunction "2_6") (pintype "passive"))
      (node (ref "OK2") (pin "5") (pinfunction "A_5") (pintype "passive"))
    )
    (net (code "77") (name "Net-(IIR2D-1)") (class "Default")
      (node (ref "IIR2") (pin "4") (pinfunction "1_4") (pintype "passive"))
      (node (ref "XI2") (pin "5") (pinfunction "SK_5") (pintype "passive"))
    )
    (net (code "78") (name "Net-(IIR2D-2)") (class "Default")
      (node (ref "IIR2") (pin "5") (pinfunction "2_5") (pintype "passive"))
      (node (ref "OK2") (pin "7") (pinfunction "A_7") (pintype "passive"))
    )
    (net (code "79") (name "Net-(INDL-PadA)") (class "Default")
      (node (ref "INDL") (pin "A") (pinfunction "A_A") (pintype "passive"))
      (node (ref "R6") (pin "2") (pinfunction "2_2") (pintype "passive"))
    )
    (net (code "80") (name "Net-(MC-PB6(XTAL1{slash}TOSC1))") (class "Default")
      (node (ref "MC") (pin "7") (pinfunction "PB6(XTAL1/TOSC1)_7") (pintype "bidirectional"))
      (node (ref "Q1") (pin "1") (pinfunction "1_1") (pintype "passive"))
    )
    (net (code "81") (name "Net-(MC-PB7(XTAL2{slash}TOSC2))") (class "Default")
      (node (ref "MC") (pin "8") (pinfunction "PB7(XTAL2/TOSC2)_8") (pintype "bidirectional"))
      (node (ref "Q1") (pin "3") (pinfunction "3_3") (pintype "passive"))
    )
    (net (code "82") (name "Net-(OD1-PadC)") (class "Default")
      (node (ref "OD1") (pin "C") (pinfunction "C_C") (pintype "passive"))
      (node (ref "OF1") (pin "2") (pinfunction "2_2") (pintype "passive"))
    )
    (net (code "83") (name "Net-(OK1A-EMIT)") (class "Default")
      (node (ref "IL1") (pin "A") (pinfunction "A_A") (pintype "passive"))
      (node (ref "OK1") (pin "15") (pinfunction "EMIT_15") (pintype "passive"))
    )
    (net (code "84") (name "Net-(OK1B-EMIT)") (class "Default")
      (node (ref "IL2") (pin "A") (pinfunction "A_A") (pintype "passive"))
      (node (ref "OK1") (pin "13") (pinfunction "EMIT_13") (pintype "passive"))
    )
    (net (code "85") (name "Net-(OK1C-EMIT)") (class "Default")
      (node (ref "IL3") (pin "A") (pinfunction "A_A") (pintype "passive"))
      (node (ref "OK1") (pin "11") (pinfunction "EMIT_11") (pintype "passive"))
    )
    (net (code "86") (name "Net-(OK1D-EMIT)") (class "Default")
      (node (ref "IL4") (pin "A") (pinfunction "A_A") (pintype "passive"))
      (node (ref "OK1") (pin "9") (pinfunction "EMIT_9") (pintype "passive"))
    )
    (net (code "87") (name "Net-(OK2A-EMIT)") (class "Default")
      (node (ref "IL5") (pin "A") (pinfunction "A_A") (pintype "passive"))
      (node (ref "OK2") (pin "15") (pinfunction "EMIT_15") (pintype "passive"))
    )
    (net (code "88") (name "Net-(OK2B-EMIT)") (class "Default")
      (node (ref "IL6") (pin "A") (pinfunction "A_A") (pintype "passive"))
      (node (ref "OK2") (pin "13") (pinfunction "EMIT_13") (pintype "passive"))
    )
    (net (code "89") (name "Net-(OK2C-EMIT)") (class "Default")
      (node (ref "IL7") (pin "A") (pinfunction "A_A") (pintype "passive"))
      (node (ref "OK2") (pin "11") (pinfunction "EMIT_11") (pintype "passive"))
    )
    (net (code "90") (name "Net-(OK2D-EMIT)") (class "Default")
      (node (ref "IL8") (pin "A") (pinfunction "A_A") (pintype "passive"))
      (node (ref "OK2") (pin "9") (pinfunction "EMIT_9") (pintype "passive"))
    )
    (net (code "91") (name "Net-(OK3A-A)") (class "Default")
      (node (ref "OK3") (pin "1") (pinfunction "A_1") (pintype "passive"))
      (node (ref "ORN1") (pin "4") (pinfunction "1_4") (pintype "passive"))
    )
    (net (code "92") (name "Net-(OK3A-C)") (class "Default")
      (node (ref "OK3") (pin "2") (pinfunction "C_2") (pintype "passive"))
      (node (ref "OL1") (pin "A") (pinfunction "A_A") (pintype "passive"))
    )
    (net (code "93") (name "Net-(OK3A-COL)") (class "Default")
      (node (ref "OK3") (pin "16") (pinfunction "COL_16") (pintype "passive"))
      (node (ref "ORN3") (pin "1") (pinfunction "1_1") (pintype "passive"))
    )
    (net (code "94") (name "Net-(OK3B-A)") (class "Default")
      (node (ref "OK3") (pin "3") (pinfunction "A_3") (pintype "passive"))
      (node (ref "ORN1") (pin "3") (pinfunction "1_3") (pintype "passive"))
    )
    (net (code "95") (name "Net-(OK3B-C)") (class "Default")
      (node (ref "OK3") (pin "4") (pinfunction "C_4") (pintype "passive"))
      (node (ref "OL2") (pin "A") (pinfunction "A_A") (pintype "passive"))
    )
    (net (code "96") (name "Net-(OK3B-COL)") (class "Default")
      (node (ref "OK3") (pin "14") (pinfunction "COL_14") (pintype "passive"))
      (node (ref "ORN3") (pin "2") (pinfunction "1_2") (pintype "passive"))
    )
    (net (code "97") (name "Net-(OK3C-A)") (class "Default")
      (node (ref "OK3") (pin "5") (pinfunction "A_5") (pintype "passive"))
      (node (ref "ORN1") (pin "2") (pinfunction "1_2") (pintype "passive"))
    )
    (net (code "98") (name "Net-(OK3C-C)") (class "Default")
      (node (ref "OK3") (pin "6") (pinfunction "C_6") (pintype "passive"))
      (node (ref "OL3") (pin "A") (pinfunction "A_A") (pintype "passive"))
    )
    (net (code "99") (name "Net-(OK3C-COL)") (class "Default")
      (node (ref "OK3") (pin "12") (pinfunction "COL_12") (pintype "passive"))
      (node (ref "ORN3") (pin "3") (pinfunction "1_3") (pintype "passive"))
    )
    (net (code "100") (name "Net-(OK3D-A)") (class "Default")
      (node (ref "OK3") (pin "7") (pinfunction "A_7") (pintype "passive"))
      (node (ref "ORN1") (pin "1") (pinfunction "1_1") (pintype "passive"))
    )
    (net (code "101") (name "Net-(OK3D-C)") (class "Default")
      (node (ref "OK3") (pin "8") (pinfunction "C_8") (pintype "passive"))
      (node (ref "OL4") (pin "A") (pinfunction "A_A") (pintype "passive"))
    )
    (net (code "102") (name "Net-(OK3D-COL)") (class "Default")
      (node (ref "OK3") (pin "10") (pinfunction "COL_10") (pintype "passive"))
      (node (ref "ORN3") (pin "4") (pinfunction "1_4") (pintype "passive"))
    )
    (net (code "103") (name "Net-(OK4A-A)") (class "Default")
      (node (ref "OK4") (pin "1") (pinfunction "A_1") (pintype "passive"))
      (node (ref "ORN4") (pin "4") (pinfunction "1_4") (pintype "passive"))
    )
    (net (code "104") (name "Net-(OK4A-C)") (class "Default")
      (node (ref "OK4") (pin "2") (pinfunction "C_2") (pintype "passive"))
      (node (ref "OL5") (pin "A") (pinfunction "A_A") (pintype "passive"))
    )
    (net (code "105") (name "Net-(OK4A-COL)") (class "Default")
      (node (ref "OK4") (pin "16") (pinfunction "COL_16") (pintype "passive"))
      (node (ref "ORN5") (pin "1") (pinfunction "1_1") (pintype "passive"))
    )
    (net (code "106") (name "Net-(OK4B-A)") (class "Default")
      (node (ref "OK4") (pin "3") (pinfunction "A_3") (pintype "passive"))
      (node (ref "ORN4") (pin "3") (pinfunction "1_3") (pintype "passive"))
    )
    (net (code "107") (name "Net-(OK4B-C)") (class "Default")
      (node (ref "OK4") (pin "4") (pinfunction "C_4") (pintype "passive"))
      (node (ref "OL6") (pin "A") (pinfunction "A_A") (pintype "passive"))
    )
    (net (code "108") (name "Net-(OK4B-COL)") (class "Default")
      (node (ref "OK4") (pin "14") (pinfunction "COL_14") (pintype "passive"))
      (node (ref "ORN5") (pin "2") (pinfunction "1_2") (pintype "passive"))
    )
    (net (code "109") (name "Net-(OK4C-A)") (class "Default")
      (node (ref "OK4") (pin "5") (pinfunction "A_5") (pintype "passive"))
      (node (ref "ORN4") (pin "2") (pinfunction "1_2") (pintype "passive"))
    )
    (net (code "110") (name "Net-(OK4C-C)") (class "Default")
      (node (ref "OK4") (pin "6") (pinfunction "C_6") (pintype "passive"))
      (node (ref "OL7") (pin "A") (pinfunction "A_A") (pintype "passive"))
    )
    (net (code "111") (name "Net-(OK4C-COL)") (class "Default")
      (node (ref "OK4") (pin "12") (pinfunction "COL_12") (pintype "passive"))
      (node (ref "ORN5") (pin "3") (pinfunction "1_3") (pintype "passive"))
    )
    (net (code "112") (name "Net-(OK4D-A)") (class "Default")
      (node (ref "OK4") (pin "7") (pinfunction "A_7") (pintype "passive"))
      (node (ref "ORN4") (pin "1") (pinfunction "1_1") (pintype "passive"))
    )
    (net (code "113") (name "Net-(OK4D-C)") (class "Default")
      (node (ref "OK4") (pin "8") (pinfunction "C_8") (pintype "passive"))
      (node (ref "OL8") (pin "A") (pinfunction "A_A") (pintype "passive"))
    )
    (net (code "114") (name "Net-(OK4D-COL)") (class "Default")
      (node (ref "OK4") (pin "10") (pinfunction "COL_10") (pintype "passive"))
      (node (ref "ORN5") (pin "4") (pinfunction "1_4") (pintype "passive"))
    )
    (net (code "115") (name "Net-(PD1-PadC)") (class "Default")
      (node (ref "PD1") (pin "C") (pinfunction "C_C") (pintype "passive"))
      (node (ref "PF1") (pin "1") (pinfunction "1_1") (pintype "passive"))
    )
    (net (code "116") (name "Net-(PIC33-OUT)") (class "Default")
      (node (ref "PCO") (pin "P$2") (pinfunction "P$2_P$2") (pintype "passive"))
      (node (ref "PD2") (pin "C") (pinfunction "C_C") (pintype "passive"))
      (node (ref "PIC33") (pin "2") (pinfunction "OUT_2") (pintype "output"))
    )
    (net (code "117") (name "Net-(PL-PadA)") (class "Default")
      (node (ref "PL") (pin "A") (pinfunction "A_A") (pintype "passive"))
      (node (ref "PR1") (pin "1") (pinfunction "1_1") (pintype "passive"))
    )
    (net (code "118") (name "Net-(U1-1C)") (class "Default")
      (node (ref "D1") (pin "2") (pinfunction "2_2") (pintype "bidirectional"))
      (node (ref "OF3") (pin "2") (pinfunction "2_2") (pintype "bidirectional"))
      (node (ref "U1") (pin "18") (pinfunction "1C_18") (pintype "output"))
    )
    (net (code "119") (name "Net-(U1-2C)") (class "Default")
      (node (ref "D1") (pin "1") (pinfunction "1_1") (pintype "bidirectional"))
      (node (ref "OF2") (pin "2") (pinfunction "2_2") (pintype "bidirectional"))
      (node (ref "U1") (pin "17") (pinfunction "2C_17") (pintype "output"))
    )
    (net (code "120") (name "Net-(U1-3C)") (class "Default")
      (node (ref "D2") (pin "2") (pinfunction "2_2") (pintype "bidirectional"))
      (node (ref "OF4") (pin "2") (pinfunction "2_2") (pintype "bidirectional"))
      (node (ref "U1") (pin "16") (pinfunction "3C_16") (pintype "output"))
    )
    (net (code "121") (name "Net-(U1-4C)") (class "Default")
      (node (ref "D2") (pin "1") (pinfunction "1_1") (pintype "bidirectional"))
      (node (ref "OF5") (pin "2") (pinfunction "2_2") (pintype "bidirectional"))
      (node (ref "U1") (pin "15") (pinfunction "4C_15") (pintype "output"))
    )
    (net (code "122") (name "Net-(U1-5C)") (class "Default")
      (node (ref "D3") (pin "2") (pinfunction "2_2") (pintype "bidirectional"))
      (node (ref "OF6") (pin "2") (pinfunction "2_2") (pintype "bidirectional"))
      (node (ref "U1") (pin "14") (pinfunction "5C_14") (pintype "output"))
    )
    (net (code "123") (name "Net-(U1-6C)") (class "Default")
      (node (ref "D3") (pin "1") (pinfunction "1_1") (pintype "bidirectional"))
      (node (ref "OF7") (pin "2") (pinfunction "2_2") (pintype "bidirectional"))
      (node (ref "U1") (pin "13") (pinfunction "6C_13") (pintype "output"))
    )
    (net (code "124") (name "Net-(U1-7C)") (class "Default")
      (node (ref "D4") (pin "2") (pinfunction "2_2") (pintype "bidirectional"))
      (node (ref "OF8") (pin "2") (pinfunction "2_2") (pintype "bidirectional"))
      (node (ref "U1") (pin "12") (pinfunction "7C_12") (pintype "output"))
    )
    (net (code "125") (name "Net-(U1-8C)") (class "Default")
      (node (ref "D4") (pin "1") (pinfunction "1_1") (pintype "bidirectional"))
      (node (ref "OF9") (pin "2") (pinfunction "2_2") (pintype "bidirectional"))
      (node (ref "U1") (pin "11") (pinfunction "8C_11") (pintype "output"))
    )
    (net (code "126") (name "Net-(XI1B-SK)") (class "Default")
      (node (ref "IIR1") (pin "1") (pinfunction "1_1") (pintype "passive"))
      (node (ref "XI1") (pin "2") (pinfunction "SK_2") (pintype "passive"))
    )
    (net (code "127") (name "Net-(XI2B-SK)") (class "Default")
      (node (ref "IIR2") (pin "1") (pinfunction "1_1") (pintype "passive"))
      (node (ref "XI2") (pin "2") (pinfunction "SK_2") (pintype "passive"))
    )
    (net (code "128") (name "Net-(XOA-SK)") (class "Default")
      (node (ref "OD1") (pin "A") (pinfunction "A_A") (pintype "passive"))
      (node (ref "XO") (pin "1") (pinfunction "SK_1") (pintype "passive"))
    )
    (net (code "129") (name "Net-(XOB-SK)") (class "Default")
      (node (ref "OF3") (pin "1") (pinfunction "1_1") (pintype "bidirectional"))
      (node (ref "XO") (pin "10") (pinfunction "SK_10") (pintype "passive"))
    )
    (net (code "130") (name "Net-(XOD-SK)") (class "Default")
      (node (ref "OF9") (pin "1") (pinfunction "1_1") (pintype "bidirectional"))
      (node (ref "XO") (pin "3") (pinfunction "SK_3") (pintype "passive"))
    )
    (net (code "131") (name "Net-(XOE-SK)") (class "Default")
      (node (ref "OF8") (pin "1") (pinfunction "1_1") (pintype "bidirectional"))
      (node (ref "XO") (pin "4") (pinfunction "SK_4") (pintype "passive"))
    )
    (net (code "132") (name "Net-(XOF-SK)") (class "Default")
      (node (ref "OF7") (pin "1") (pinfunction "1_1") (pintype "bidirectional"))
      (node (ref "XO") (pin "5") (pinfunction "SK_5") (pintype "passive"))
    )
    (net (code "133") (name "Net-(XOG-SK)") (class "Default")
      (node (ref "OF6") (pin "1") (pinfunction "1_1") (pintype "bidirectional"))
      (node (ref "XO") (pin "6") (pinfunction "SK_6") (pintype "passive"))
    )
    (net (code "134") (name "Net-(XOH-SK)") (class "Default")
      (node (ref "OF5") (pin "1") (pinfunction "1_1") (pintype "bidirectional"))
      (node (ref "XO") (pin "7") (pinfunction "SK_7") (pintype "passive"))
    )
    (net (code "135") (name "Net-(XOI-SK)") (class "Default")
      (node (ref "OF4") (pin "1") (pinfunction "1_1") (pintype "bidirectional"))
      (node (ref "XO") (pin "8") (pinfunction "SK_8") (pintype "passive"))
    )
    (net (code "136") (name "Net-(XOJ-SK)") (class "Default")
      (node (ref "OF2") (pin "1") (pinfunction "1_1") (pintype "bidirectional"))
      (node (ref "XO") (pin "9") (pinfunction "SK_9") (pintype "passive"))
    )
    (net (code "137") (name "OI1") (class "Default")
      (node (ref "OK3") (pin "15") (pinfunction "EMIT_15") (pintype "passive"))
      (node (ref "ORN2") (pin "1") (pinfunction "1_1") (pintype "passive"))
      (node (ref "U1") (pin "8") (pinfunction "8B_8") (pintype "input"))
    )
    (net (code "138") (name "OI2") (class "Default")
      (node (ref "OK3") (pin "13") (pinfunction "EMIT_13") (pintype "passive"))
      (node (ref "ORN2") (pin "2") (pinfunction "1_2") (pintype "passive"))
      (node (ref "U1") (pin "7") (pinfunction "7B_7") (pintype "input"))
    )
    (net (code "139") (name "OI3") (class "Default")
      (node (ref "OK3") (pin "11") (pinfunction "EMIT_11") (pintype "passive"))
      (node (ref "ORN2") (pin "3") (pinfunction "1_3") (pintype "passive"))
      (node (ref "U1") (pin "6") (pinfunction "6B_6") (pintype "input"))
    )
    (net (code "140") (name "OI4") (class "Default")
      (node (ref "OK3") (pin "9") (pinfunction "EMIT_9") (pintype "passive"))
      (node (ref "ORN2") (pin "4") (pinfunction "1_4") (pintype "passive"))
      (node (ref "U1") (pin "5") (pinfunction "5B_5") (pintype "input"))
    )
    (net (code "141") (name "RAW_IV") (class "Default")
      (node (ref "GPIO") (pin "1") (pinfunction "S_1") (pintype "passive"))
      (node (ref "PC1") (pin "+") (pinfunction "+_+") (pintype "passive"))
      (node (ref "PF1") (pin "2") (pinfunction "2_2") (pintype "passive"))
      (node (ref "PIC33") (pin "1") (pinfunction "VIN_1") (pintype "input"))
    )
    (net (code "142") (name "RESET") (class "Default")
      (node (ref "BL") (pin "5") (pinfunction "S_5") (pintype "passive"))
      (node (ref "C2") (pin "1") (pinfunction "1_1") (pintype "passive"))
      (node (ref "MC") (pin "29") (pinfunction "PC6(/RESET)_29") (pintype "bidirectional"))
      (node (ref "R2") (pin "1") (pinfunction "1_1") (pintype "passive"))
      (node (ref "SR") (pin "1") (pinfunction "P_1") (pintype "passive"))
    )
    (net (code "143") (name "RXI") (class "Default")
      (node (ref "MC") (pin "30") (pinfunction "PD0(RXD)_30") (pintype "bidirectional"))
      (node (ref "PP") (pin "4") (pinfunction "S_4") (pintype "passive"))
    )
    (net (code "144") (name "TXO") (class "Default")
      (node (ref "MC") (pin "31") (pinfunction "PD1(TXD)_31") (pintype "bidirectional"))
      (node (ref "PP") (pin "3") (pinfunction "S_3") (pintype "passive"))
    )
    (net (code "145") (name "VDDO") (class "Default")
      (node (ref "D1") (pin "3") (pinfunction "3_3") (pintype "bidirectional"))
      (node (ref "D2") (pin "3") (pinfunction "3_3") (pintype "bidirectional"))
      (node (ref "D3") (pin "3") (pinfunction "3_3") (pintype "bidirectional"))
      (node (ref "D4") (pin "3") (pinfunction "3_3") (pintype "bidirectional"))
      (node (ref "EC6") (pin "+") (pinfunction "+_+") (pintype "passive"))
      (node (ref "OD2") (pin "C") (pinfunction "C_C") (pintype "passive"))
      (node (ref "OF1") (pin "1") (pinfunction "1_1") (pintype "passive"))
      (node (ref "ORN3") (pin "5") (pinfunction "2_5") (pintype "passive"))
      (node (ref "ORN3") (pin "6") (pinfunction "2_6") (pintype "passive"))
      (node (ref "ORN3") (pin "7") (pinfunction "2_7") (pintype "passive"))
      (node (ref "ORN3") (pin "8") (pinfunction "2_8") (pintype "passive"))
      (node (ref "ORN5") (pin "5") (pinfunction "2_5") (pintype "passive"))
      (node (ref "ORN5") (pin "6") (pinfunction "2_6") (pintype "passive"))
      (node (ref "ORN5") (pin "7") (pinfunction "2_7") (pintype "passive"))
      (node (ref "ORN5") (pin "8") (pinfunction "2_8") (pintype "passive"))
      (node (ref "U1") (pin "10") (pinfunction "COM_10") (pintype "output"))
    )
    (net (code "146") (name "VIN") (class "Default")
      (node (ref "PD1") (pin "A") (pinfunction "A_A") (pintype "passive"))
      (node (ref "PJ1") (pin "VIN0") (pinfunction "PWR_VIN0") (pintype "bidirectional"))
      (node (ref "XV") (pin "2") (pinfunction "SK_2") (pintype "passive"))
    )
    (net (code "147") (name "WFGPIO0") (class "Default")
      (node (ref "GPIO") (pin "13") (pinfunction "S_13") (pintype "passive"))
      (node (ref "WIFI") (pin "GPIO0") (pinfunction "GPIO0_GPIO0") (pintype "bidirectional"))
    )
    (net (code "148") (name "WFGPIO2") (class "Default")
      (node (ref "GPIO") (pin "14") (pinfunction "S_14") (pintype "passive"))
      (node (ref "WIFI") (pin "GPIO2") (pinfunction "GPIO2_GPIO2") (pintype "bidirectional"))
    )
    (net (code "149") (name "unconnected-(ENC-CLKOUT-Pad3)") (class "Default")
      (node (ref "ENC") (pin "3") (pinfunction "CLKOUT_3") (pintype "output"))
    )
    (net (code "150") (name "unconnected-(ENC-WOL-Pad5)") (class "Default")
      (node (ref "ENC") (pin "5") (pinfunction "WOL_5") (pintype "output"))
    )
    (net (code "151") (name "unconnected-(IC1-INTA-Pad20)") (class "Default")
      (node (ref "IC1") (pin "20") (pinfunction "INTA_20") (pintype "output"))
    )
    (net (code "152") (name "unconnected-(IC1-INTB-Pad19)") (class "Default")
      (node (ref "IC1") (pin "19") (pinfunction "INTB_19") (pintype "output"))
    )
    (net (code "153") (name "unconnected-(PJ1-GND-PadP$4)") (class "Default")
      (node (ref "PJ1") (pin "P$4") (pinfunction "GND_P$4") (pintype "bidirectional"))
    )
    (net (code "154") (name "unconnected-(U$2-PadNC)") (class "Default")
      (node (ref "U$2") (pin "NC") (pinfunction "NC_NC") (pintype "bidirectional"))
    )
    (net (code "155") (name "unconnected-(WIFI-PadRST)") (class "Default")
      (node (ref "WIFI") (pin "RST") (pinfunction "RST_RST") (pintype "bidirectional"))
    )
  )
)
